# IR.net
KiCad netlist of a schematic drawn in Altium Designer
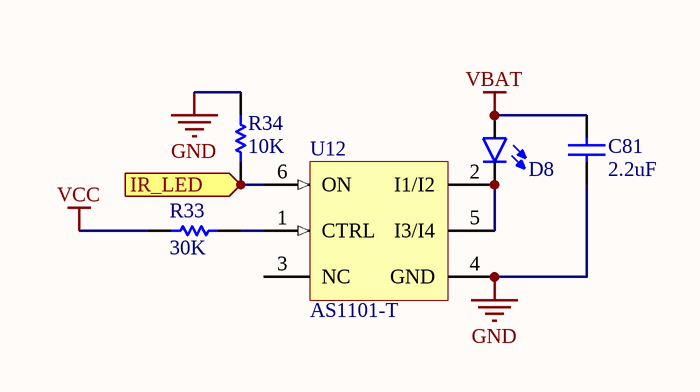
[diagram p0: IR.SchDoc]

(export (version "E")
  (design (tool "Eeschema 10.0.6"))
  (components
    (comp (ref "C81")
      (value "2.2uF")
      (footprint "C0402[1005X55]")
      (description "2.2uF 6.3V 20% 0402 (1005 Metric)")
      (fields (field (name "PARTNUMBER") "GRM155R60J225ME15D") (field (name "MANUFACTURER") "Murata"))
      (libsource (lib "Capacitors") (part "CAP_2.2uF_6.3V_0402_20%"))
    )
    (comp (ref "D8")
      (value "SFH 4046")
      (footprint "LED1206")
      (fields (field (name "MANUFACTURER") "Osram"))
      (libsource (lib "LEDs") (part "SFH 4046"))
    )
    (comp (ref "R33")
      (value "30K")
      (footprint "R0402[1005]")
      (description "30K 0.063W 1% 0402 (1005 Metric)")
      (fields (field (name "MANUFACTURER") "KOA Speer") (field (name "PARTNUMBER") "RK73H1ETTP3002F"))
      (libsource (lib "Resistors") (part "RES_30K_0402_1%"))
    )
    (comp (ref "R34")
      (value "10K")
      (footprint "R0402[1005]")
      (description "10K 0.063W 1% 0402 (1005 Metric)")
      (fields (field (name "MANUFACTURER") "KOA Speer") (field (name "PARTNUMBER") "RK73H1ETTP1002F"))
      (libsource (lib "Resistors") (part "RES_10K_0402_1%"))
    )
    (comp (ref "U12")
      (value "AS1101-T")
      (footprint "AMS-SC70-6-2000X1250DE_N")
      (description "80 mA, Simple Drive, Dual LED Driver with Enable, 2.2 to 3.6 V, SC70-6, Reel")
      (fields (field (name "MANUFACTURER") "AMS"))
      (libsource (lib "Altium Content Vault") (part "AMS-AS1101-SC70-6"))
    )
  )
  (nets
    (net (code "1") (name "/IR_LED") (class "Default")
      (node (ref "R34") (pin "1") (pinfunction "1_1") (pintype "passive"))
      (node (ref "U12") (pin "6") (pinfunction "ON_6") (pintype "input"))
    )
    (net (code "2") (name "GND") (class "Default")
      (node (ref "C81") (pin "1") (pinfunction "1_1") (pintype "passive"))
      (node (ref "R34") (pin "2") (pinfunction "2_2") (pintype "passive"))
      (node (ref "U12") (pin "4") (pinfunction "GND_4") (pintype "power_in"))
    )
    (net (code "3") (name "Net-(U12-CTRL)") (class "Default")
      (node (ref "R33") (pin "2") (pinfunction "2_2") (pintype "passive"))
      (node (ref "U12") (pin "1") (pinfunction "CTRL_1") (pintype "input"))
    )
    (net (code "4") (name "Net-(U12-I1{slash}I2)") (class "Default")
      (node (ref "D8") (pin "C") (pinfunction "C_C") (pintype "passive"))
      (node (ref "U12") (pin "2") (pinfunction "I1/I2_2") (pintype "passive"))
      (node (ref "U12") (pin "5") (pinfunction "I3/I4_5") (pintype "passive"))
    )
    (net (code "5") (name "VBAT") (class "Default")
      (node (ref "C81") (pin "2") (pinfunction "2_2") (pintype "passive"))
      (node (ref "D8") (pin "A") (pinfunction "A_A") (pintype "passive"))
    )
    (net (code "6") (name "VCC") (class "Default")
      (node (ref "R33") (pin "1") (pinfunction "1_1") (pintype "passive"))
    )
    (net (code "7") (name "unconnected-(U12-NC-Pad3)") (class "Default")
      (node (ref "U12") (pin "3") (pinfunction "NC_3") (pintype "passive"))
    )
  )
)
